# wiPOWER.net
KiCad netlist of a schematic drawn in EAGLE
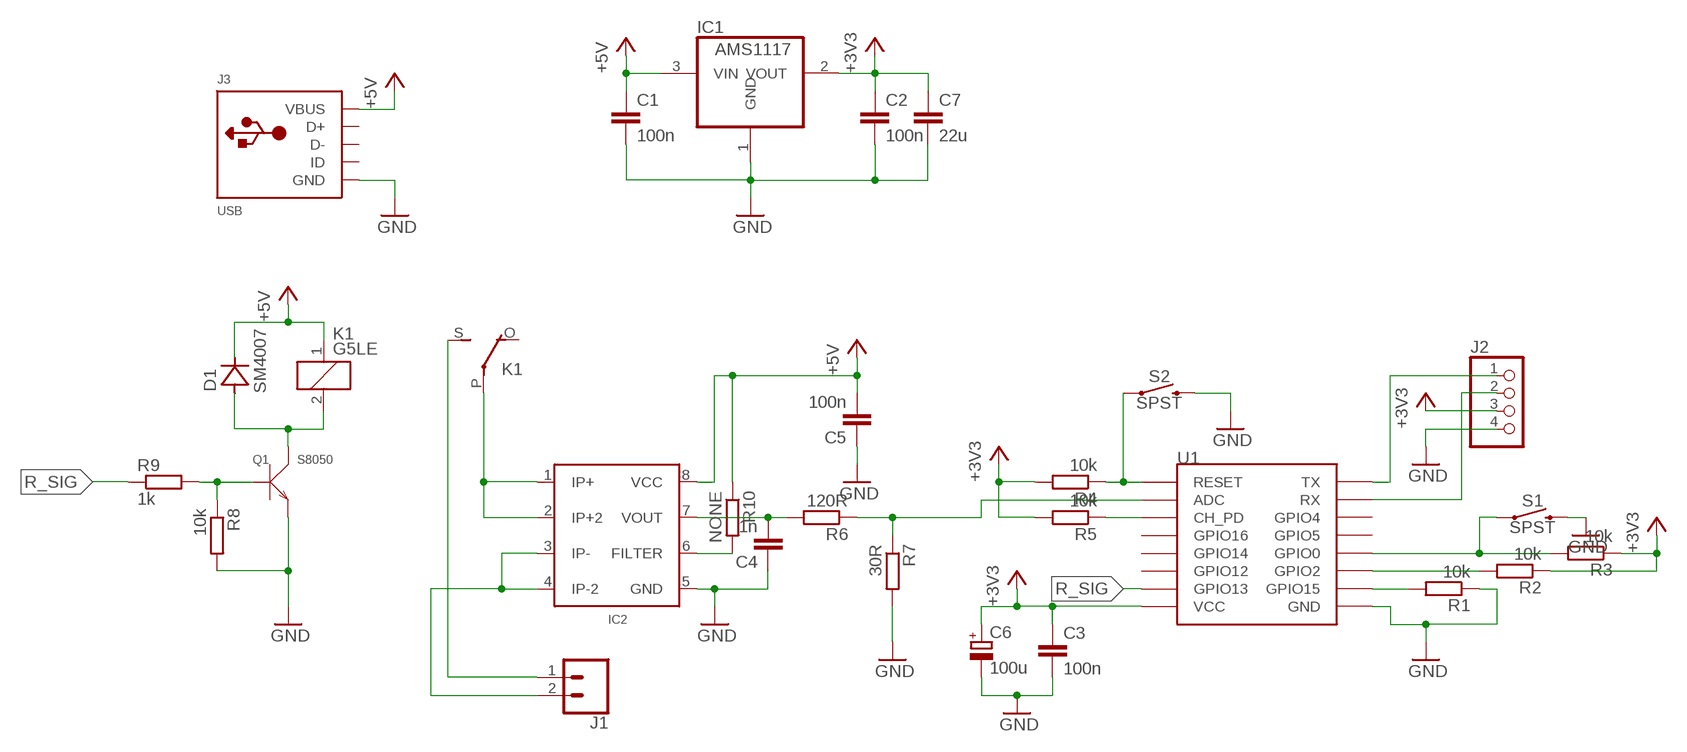
[diagram p0: schematic, sheet 1]

(export (version "E")
  (design (tool "Eeschema 10.0.6"))
  (components
    (comp (ref "C1")
      (value "100n")
      (footprint "eagle-import:C0603")
      (libsource (lib "eagle-import") (part "C-EUC0603"))
    )
    (comp (ref "C2")
      (value "100n")
      (footprint "eagle-import:C0603")
      (libsource (lib "eagle-import") (part "C-EUC0603"))
    )
    (comp (ref "C3")
      (value "100n")
      (footprint "eagle-import:C0603")
      (libsource (lib "eagle-import") (part "C-EUC0603"))
    )
    (comp (ref "C4")
      (value "1n")
      (footprint "eagle-import:C0603")
      (libsource (lib "eagle-import") (part "C-EUC0603"))
    )
    (comp (ref "C5")
      (value "100n")
      (footprint "eagle-import:C0603")
      (libsource (lib "eagle-import") (part "C-EUC0603"))
    )
    (comp (ref "C6")
      (value "100u")
      (footprint "eagle-import:B_3528-21R")
      (libsource (lib "eagle-import") (part "CPOL-EUB/3528-21R"))
    )
    (comp (ref "C7")
      (value "22u")
      (footprint "eagle-import:C0603")
      (libsource (lib "eagle-import") (part "C-EUC0603"))
    )
    (comp (ref "D1")
      (value "SM4007")
      (footprint "eagle-import:DIODE_SOD123")
      (libsource (lib "eagle-import") (part "SM4007PL"))
    )
    (comp (ref "IC1")
      (value "AMS1117")
      (footprint "eagle-import:SOT223")
      (fields (field (name "MPN") "REG1117"))
      (libsource (lib "eagle-import") (part "REG1117"))
    )
    (comp (ref "IC2")
      (value "ACS712SOIC8")
      (footprint "eagle-import:SOIC8")
      (libsource (lib "eagle-import") (part "ACS712SOIC8"))
    )
    (comp (ref "J1")
      (value "CONN_025MM")
      (footprint "eagle-import:SCREWTERMINAL-5MM-2")
      (libsource (lib "eagle-import") (part "CONN_025MM"))
    )
    (comp (ref "J2")
      (value "PINHD-1X4")
      (footprint "eagle-import:1X04")
      (libsource (lib "eagle-import") (part "PINHD-1X4"))
    )
    (comp (ref "J3")
      (value "USB")
      (footprint "eagle-import:MIC-USB")
      (libsource (lib "eagle-import") (part "USB-MICRO"))
    )
    (comp (ref "K1")
      (value "G5LE")
      (footprint "eagle-import:G5LE")
      (libsource (lib "eagle-import") (part "G5LE"))
    )
    (comp (ref "Q1")
      (value "S8050")
      (footprint "eagle-import:SOT-23")
      (libsource (lib "eagle-import") (part "SMD-TRANSISTORS-NPN-25V-500MW-S8050(SOT-23)"))
    )
    (comp (ref "R1")
      (value "10k")
      (footprint "eagle-import:R0603")
      (libsource (lib "eagle-import") (part "R-EU_R0603"))
    )
    (comp (ref "R2")
      (value "10k")
      (footprint "eagle-import:R0603")
      (libsource (lib "eagle-import") (part "R-EU_R0603"))
    )
    (comp (ref "R3")
      (value "10k")
      (footprint "eagle-import:R0603")
      (libsource (lib "eagle-import") (part "R-EU_R0603"))
    )
    (comp (ref "R4")
      (value "10k")
      (footprint "eagle-import:R0603")
      (libsource (lib "eagle-import") (part "R-EU_R0603"))
    )
    (comp (ref "R5")
      (value "10k")
      (footprint "eagle-import:R0603")
      (libsource (lib "eagle-import") (part "R-EU_R0603"))
    )
    (comp (ref "R6")
      (value "120R")
      (footprint "eagle-import:R0603")
      (libsource (lib "eagle-import") (part "R-EU_R0603"))
    )
    (comp (ref "R7")
      (value "30R")
      (footprint "eagle-import:R0603")
      (libsource (lib "eagle-import") (part "R-EU_R0603"))
    )
    (comp (ref "R8")
      (value "10k")
      (footprint "eagle-import:R0603")
      (libsource (lib "eagle-import") (part "R-EU_R0603"))
    )
    (comp (ref "R9")
      (value "1k")
      (footprint "eagle-import:R0603")
      (libsource (lib "eagle-import") (part "R-EU_R0603"))
    )
    (comp (ref "R10")
      (value "NONE")
      (footprint "eagle-import:R0603")
      (libsource (lib "eagle-import") (part "R-EU_R0603"))
    )
    (comp (ref "S1")
      (value "SPST")
      (footprint "eagle-import:TACTILE_SWITCH_SMD_6.0X3.5MM")
      (libsource (lib "eagle-import") (part "MOMENTARY-SWITCH-SPST-SMD-6.0X3.5MM"))
    )
    (comp (ref "S2")
      (value "SPST")
      (footprint "eagle-import:TACTILE_SWITCH_SMD_6.0X3.5MM")
      (libsource (lib "eagle-import") (part "MOMENTARY-SWITCH-SPST-SMD-6.0X3.5MM"))
    )
    (comp (ref "U1")
      (value "ESP12SMD")
      (footprint "eagle-import:ESP12-SMD")
      (libsource (lib "eagle-import") (part "ESP12SMD"))
    )
  )
  (nets
    (net (code "1") (name "+3V3") (class "Default")
      (node (ref "C2") (pin "1") (pinfunction "1_1") (pintype "passive"))
      (node (ref "C3") (pin "1") (pinfunction "1_1") (pintype "passive"))
      (node (ref "C6") (pin "+") (pinfunction "+_+") (pintype "passive"))
      (node (ref "C7") (pin "1") (pinfunction "1_1") (pintype "passive"))
      (node (ref "IC1") (pin "2") (pinfunction "VOUT_2") (pintype "output"))
      (node (ref "J2") (pin "3") (pinfunction "3_3") (pintype "passive"))
      (node (ref "R2") (pin "1") (pinfunction "1_1") (pintype "passive"))
      (node (ref "R3") (pin "1") (pinfunction "1_1") (pintype "passive"))
      (node (ref "R4") (pin "2") (pinfunction "2_2") (pintype "passive"))
      (node (ref "R5") (pin "2") (pinfunction "2_2") (pintype "passive"))
      (node (ref "U1") (pin "VCC") (pinfunction "VCC_VCC") (pintype "bidirectional"))
    )
    (net (code "2") (name "+5V") (class "Default")
      (node (ref "C1") (pin "1") (pinfunction "1_1") (pintype "passive"))
      (node (ref "C5") (pin "2") (pinfunction "2_2") (pintype "passive"))
      (node (ref "D1") (pin "C") (pinfunction "C_C") (pintype "passive"))
      (node (ref "IC1") (pin "3") (pinfunction "VIN_3") (pintype "input"))
      (node (ref "IC2") (pin "8") (pinfunction "VCC_8") (pintype "power_in"))
      (node (ref "J3") (pin "P$5") (pinfunction "VBUS_P$5") (pintype "power_in"))
      (node (ref "K1") (pin "1") (pinfunction "1_1") (pintype "passive"))
      (node (ref "R10") (pin "1") (pinfunction "1_1") (pintype "passive"))
    )
    (net (code "3") (name "GND") (class "Default")
      (node (ref "C1") (pin "2") (pinfunction "2_2") (pintype "passive"))
      (node (ref "C2") (pin "2") (pinfunction "2_2") (pintype "passive"))
      (node (ref "C3") (pin "2") (pinfunction "2_2") (pintype "passive"))
      (node (ref "C4") (pin "1") (pinfunction "1_1") (pintype "passive"))
      (node (ref "C5") (pin "1") (pinfunction "1_1") (pintype "passive"))
      (node (ref "C6") (pin "-") (pinfunction "-_-") (pintype "passive"))
      (node (ref "C7") (pin "2") (pinfunction "2_2") (pintype "passive"))
      (node (ref "IC1") (pin "1") (pinfunction "GND_1") (pintype "power_in"))
      (node (ref "IC2") (pin "5") (pinfunction "GND_5") (pintype "power_in"))
      (node (ref "J2") (pin "4") (pinfunction "4_4") (pintype "passive"))
      (node (ref "J3") (pin "P$2") (pinfunction "GND_P$2") (pintype "power_in"))
      (node (ref "Q1") (pin "2") (pinfunction "E_2") (pintype "passive"))
      (node (ref "R1") (pin "1") (pinfunction "1_1") (pintype "passive"))
      (node (ref "R7") (pin "2") (pinfunction "2_2") (pintype "passive"))
      (node (ref "R8") (pin "2") (pinfunction "2_2") (pintype "passive"))
      (node (ref "S1") (pin "2") (pinfunction "2_2") (pintype "passive"))
      (node (ref "S2") (pin "2") (pinfunction "2_2") (pintype "passive"))
      (node (ref "U1") (pin "GND") (pinfunction "GND_GND") (pintype "bidirectional"))
    )
    (net (code "4") (name "Net-(IC2-FILTER)") (class "Default")
      (node (ref "IC2") (pin "6") (pinfunction "FILTER_6") (pintype "bidirectional"))
      (node (ref "R10") (pin "2") (pinfunction "2_2") (pintype "passive"))
    )
    (net (code "5") (name "Net-(IC2-IP+)") (class "Default")
      (node (ref "IC2") (pin "1") (pinfunction "IP+_1") (pintype "bidirectional"))
      (node (ref "IC2") (pin "2") (pinfunction "IP+2_2") (pintype "bidirectional"))
      (node (ref "K1") (pin "P") (pinfunction "P_P") (pintype "passive"))
    )
    (net (code "6") (name "Net-(IC2-IP-)") (class "Default")
      (node (ref "IC2") (pin "3") (pinfunction "IP-_3") (pintype "bidirectional"))
      (node (ref "IC2") (pin "4") (pinfunction "IP-2_4") (pintype "bidirectional"))
      (node (ref "J1") (pin "2") (pinfunction "2_2") (pintype "passive"))
    )
    (net (code "7") (name "Net-(IC2-VOUT)") (class "Default")
      (node (ref "C4") (pin "2") (pinfunction "2_2") (pintype "passive"))
      (node (ref "IC2") (pin "7") (pinfunction "VOUT_7") (pintype "bidirectional"))
      (node (ref "R6") (pin "2") (pinfunction "2_2") (pintype "passive"))
    )
    (net (code "8") (name "Net-(J1-Pad1)") (class "Default")
      (node (ref "J1") (pin "1") (pinfunction "1_1") (pintype "passive"))
      (node (ref "K1") (pin "S") (pinfunction "S_S") (pintype "passive"))
    )
    (net (code "9") (name "Net-(Q1-B)") (class "Default")
      (node (ref "Q1") (pin "1") (pinfunction "B_1") (pintype "passive"))
      (node (ref "R8") (pin "1") (pinfunction "1_1") (pintype "passive"))
      (node (ref "R9") (pin "2") (pinfunction "2_2") (pintype "passive"))
    )
    (net (code "10") (name "Net-(Q1-C)") (class "Default")
      (node (ref "D1") (pin "A") (pinfunction "A_A") (pintype "passive"))
      (node (ref "K1") (pin "2") (pinfunction "2_2") (pintype "passive"))
      (node (ref "Q1") (pin "3") (pinfunction "C_3") (pintype "passive"))
    )
    (net (code "11") (name "Net-(R1-Pad2)") (class "Default")
      (node (ref "R1") (pin "2") (pinfunction "2_2") (pintype "passive"))
      (node (ref "U1") (pin "GPIO15") (pinfunction "GPIO15_GPIO15") (pintype "bidirectional"))
    )
    (net (code "12") (name "Net-(R2-Pad2)") (class "Default")
      (node (ref "R2") (pin "2") (pinfunction "2_2") (pintype "passive"))
      (node (ref "U1") (pin "GPIO2") (pinfunction "GPIO2_GPIO2") (pintype "bidirectional"))
    )
    (net (code "13") (name "Net-(R3-Pad2)") (class "Default")
      (node (ref "R3") (pin "2") (pinfunction "2_2") (pintype "passive"))
      (node (ref "S1") (pin "1") (pinfunction "1_1") (pintype "passive"))
      (node (ref "U1") (pin "GPIO0") (pinfunction "GPIO0_GPIO0") (pintype "bidirectional"))
    )
    (net (code "14") (name "Net-(R4-Pad1)") (class "Default")
      (node (ref "R4") (pin "1") (pinfunction "1_1") (pintype "passive"))
      (node (ref "S2") (pin "1") (pinfunction "1_1") (pintype "passive"))
      (node (ref "U1") (pin "RESET") (pinfunction "RESET_RESET") (pintype "bidirectional"))
    )
    (net (code "15") (name "Net-(R5-Pad1)") (class "Default")
      (node (ref "R5") (pin "1") (pinfunction "1_1") (pintype "passive"))
      (node (ref "U1") (pin "CH_PD") (pinfunction "CH_PD_CH_PD") (pintype "bidirectional"))
    )
    (net (code "16") (name "Net-(R6-Pad1)") (class "Default")
      (node (ref "R6") (pin "1") (pinfunction "1_1") (pintype "passive"))
      (node (ref "R7") (pin "1") (pinfunction "1_1") (pintype "passive"))
      (node (ref "U1") (pin "ADC") (pinfunction "ADC_ADC") (pintype "bidirectional"))
    )
    (net (code "17") (name "Net-(U1-RX)") (class "Default")
      (node (ref "J2") (pin "2") (pinfunction "2_2") (pintype "passive"))
      (node (ref "U1") (pin "RXD0") (pinfunction "RX_RXD0") (pintype "bidirectional"))
    )
    (net (code "18") (name "Net-(U1-TX)") (class "Default")
      (node (ref "J2") (pin "1") (pinfunction "1_1") (pintype "passive"))
      (node (ref "U1") (pin "TXD0") (pinfunction "TX_TXD0") (pintype "bidirectional"))
    )
    (net (code "19") (name "R_SIG") (class "Default")
      (node (ref "R9") (pin "1") (pinfunction "1_1") (pintype "passive"))
      (node (ref "U1") (pin "GPIO13") (pinfunction "GPIO13_GPIO13") (pintype "bidirectional"))
    )
    (net (code "20") (name "unconnected-(J3-D+-PadP$3)") (class "Default")
      (node (ref "J3") (pin "P$3") (pinfunction "D+_P$3") (pintype "bidirectional"))
    )
    (net (code "21") (name "unconnected-(J3-D--PadP$4)") (class "Default")
      (node (ref "J3") (pin "P$4") (pinfunction "D-_P$4") (pintype "bidirectional"))
    )
    (net (code "22") (name "unconnected-(J3-ID-PadP$1)") (class "Default")
      (node (ref "J3") (pin "P$1") (pinfunction "ID_P$1") (pintype "bidirectional"))
    )
    (net (code "23") (name "unconnected-(K1-PadO)") (class "Default")
      (node (ref "K1") (pin "O") (pinfunction "O_O") (pintype "passive"))
    )
    (net (code "24") (name "unconnected-(U1-PadGPIO4)") (class "Default")
      (node (ref "U1") (pin "GPIO4") (pinfunction "GPIO4_GPIO4") (pintype "bidirectional"))
    )
    (net (code "25") (name "unconnected-(U1-PadGPIO5)") (class "Default")
      (node (ref "U1") (pin "GPIO5") (pinfunction "GPIO5_GPIO5") (pintype "bidirectional"))
    )
    (net (code "26") (name "unconnected-(U1-PadGPIO12)") (class "Default")
      (node (ref "U1") (pin "GPIO12") (pinfunction "GPIO12_GPIO12") (pintype "bidirectional"))
    )
    (net (code "27") (name "unconnected-(U1-PadGPIO14)") (class "Default")
      (node (ref "U1") (pin "GPIO14") (pinfunction "GPIO14_GPIO14") (pintype "bidirectional"))
    )
    (net (code "28") (name "unconnected-(U1-PadGPIO16)") (class "Default")
      (node (ref "U1") (pin "GPIO16") (pinfunction "GPIO16_GPIO16") (pintype "bidirectional"))
    )
  )
)
